# gateway.net
KiCad netlist of a schematic drawn in Altium Designer
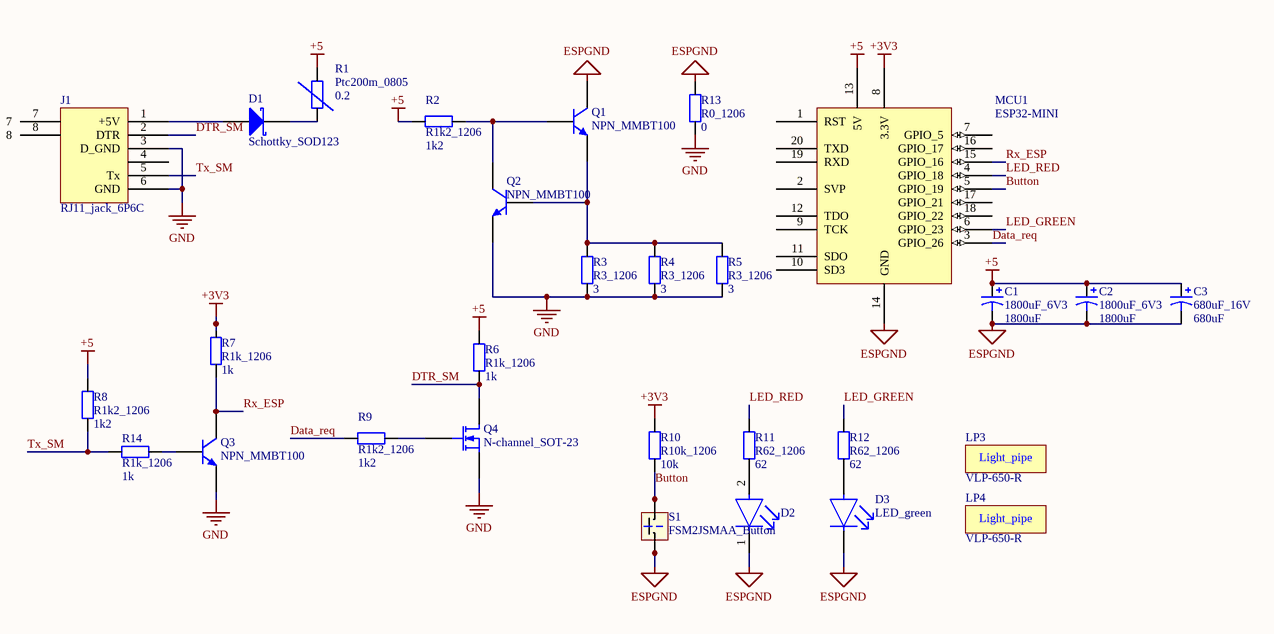
[diagram p0: gateway.SchDoc]

(export (version "E")
  (design (tool "Eeschema 10.0.6"))
  (components
    (comp (ref "C1")
      (value "1800uF_6V3")
      (footprint "CAPAE109103X105M_680uF")
      (description "SMD Aluminium Electrolytic Capacitor, Radial Can, 1800 µF, 10 V, 0.092 ohm, TRV Series")
      (fields
        (field (name "MANUFACTURER PART NUMBER") "EEE-FN0J182UV")
        (field (name "MANUFACTURER") "Panasonic")
        (field (name "ALTIUM_VALUE") "1800uF")
      )
      (libsource (lib "Capacitor") (part "1800uF_6V3"))
    )
    (comp (ref "C2")
      (value "1800uF_6V3")
      (footprint "CAPAE109103X105M_680uF")
      (description "SMD Aluminium Electrolytic Capacitor, Radial Can, 1800 µF, 10 V, 0.092 ohm, TRV Series")
      (fields
        (field (name "MANUFACTURER PART NUMBER") "EEE-FN0J182UV")
        (field (name "MANUFACTURER") "Panasonic")
        (field (name "ALTIUM_VALUE") "1800uF")
      )
      (libsource (lib "Capacitor") (part "1800uF_6V3"))
    )
    (comp (ref "C3")
      (value "680uF_16V")
      (footprint "CAPAE109103X105M_680uF")
      (description "Aluminum Electrolytic Capacitors - SMD LOW ESR ELECTROLYTIC CAPACITORS")
      (fields
        (field (name "MANUFACTURER PART NUMBER") "16TZV680M10X10.5")
        (field (name "MANUFACTURER") "Rubycon")
        (field (name "ALTIUM_VALUE") "680uF")
      )
      (libsource (lib "Capacitor") (part "680uF_16V"))
    )
    (comp (ref "D1")
      (value "Schottky_SOD123")
      (footprint "Diode_SOD-123")
      (description "Schottky Rectifier, 20 V, 500 mA, Single, SOD-123, 2 Pins, 320 mV")
      (fields
        (field (name "MANUFACTURER PART NUMBER") "STPS0520Z")
        (field (name "MANUFACTURER") "STMicroelectronics")
      )
      (libsource (lib "Diodes") (part "Schottky_SOD123"))
    )
    (comp (ref "D2")
      (value "red led")
      (footprint "Kingbright_KPT-2012EC_0")
      (description "KPT-2012EC -  LED, Low Power, Red, SMD, 0805 [2012 Metric], 30 mA, 2 V, 617 nm")
      (fields
        (field (name "MANUFACTURER PART NUMBER") "AP2012SRCPRV")
        (field (name "MANUFACTURER") "Kingbright")
      )
      (libsource (lib "Button_led") (part "KPT-2012EC"))
    )
    (comp (ref "D3")
      (value "LED_green")
      (footprint "Kingbright_KPT-2012EC_0")
      (description "Standard LEDs - SMD GRN WATER CLEAR 0805")
      (fields
        (field (name "MANUFACTURER") "Kingbright")
        (field (name "MANUFACTURER PART NUMBER") "AP2012MGC")
      )
      (libsource (lib "Button_led") (part "LED_green"))
    )
    (comp (ref "J1")
      (value "RJ11_jack_6P6C")
      (footprint "44144-0005")
      (description "Modular Connector, RJ11 Jack, 1 x 1 (Port), 6P6C, Cat3, Surface Mount")
      (fields (field (name "MANUFACTURER PART NUMBER") "44144-0005") (field (name "MANUFACTURER") "Molex"))
      (libsource (lib "Connectors") (part "RJ11_jack_6P6C"))
    )
    (comp (ref "LP3")
      (value "VLP-650-R")
      (footprint "VLP-650-R")
      (description "LED Light Pipes Light Pipe Bd Mount SMD .65\" Round Face")
      (fields (field (name "MANUFACTURER") "Bivar"))
      (libsource (lib "Button_led") (part "VLP-650-R"))
    )
    (comp (ref "LP4")
      (value "VLP-650-R")
      (footprint "VLP-650-R")
      (description "LED Light Pipes Light Pipe Bd Mount SMD .65\" Round Face")
      (fields (field (name "MANUFACTURER") "Bivar"))
      (libsource (lib "Button_led") (part "VLP-650-R"))
    )
    (comp (ref "MCU1")
      (value "ESP32-MINI")
      (footprint "PINHEADERS_SMD_10")
      (description "LilyGO TTGO T7 Mini32 V1.4 ESP32-WROVER")
      (fields (field (name "MANUFACTURER PART NUMBER") "10129380-910002ALF"))
      (libsource (lib "mcu") (part "ESP32-MINI"))
    )
    (comp (ref "Q1")
      (value "NPN_MMBT100")
      (footprint "SOT95P245X110-3N")
      (description "Bipolar (BJT) Single Transistor, NPN, 45 V, 500 mA, 350 mW, SOT-23, Surface Mount")
      (fields
        (field (name "MANUFACTURER PART NUMBER") "MMBT100")
        (field (name "MANUFACTURER") "ON Semiconductor / Fairchild")
      )
      (libsource (lib "Transistor") (part "NPN_MMBT100"))
    )
    (comp (ref "Q2")
      (value "NPN_MMBT100")
      (footprint "SOT95P245X110-3N")
      (description "Bipolar (BJT) Single Transistor, NPN, 45 V, 500 mA, 350 mW, SOT-23, Surface Mount")
      (fields
        (field (name "MANUFACTURER PART NUMBER") "MMBT100")
        (field (name "MANUFACTURER") "ON Semiconductor / Fairchild")
      )
      (libsource (lib "Transistor") (part "NPN_MMBT100"))
    )
    (comp (ref "Q3")
      (value "NPN_MMBT100")
      (footprint "SOT95P245X110-3N")
      (description "Bipolar (BJT) Single Transistor, NPN, 45 V, 500 mA, 350 mW, SOT-23, Surface Mount")
      (fields
        (field (name "MANUFACTURER PART NUMBER") "MMBT100")
        (field (name "MANUFACTURER") "ON Semiconductor / Fairchild")
      )
      (libsource (lib "Transistor") (part "NPN_MMBT100"))
    )
    (comp (ref "Q4")
      (value "N-channel_SOT-23")
      (footprint "SOT95P237X110-3N")
      (description "Power MOSFET, N Channel, 60 V, 260 mA, 1 ohm, SOT-23, Surface Mount")
      (fields
        (field (name "MANUFACTURER PART NUMBER") "NTR5103NT1G")
        (field (name "MANUFACTURER") "ON Semiconductor")
      )
      (libsource (lib "Mosfet") (part "N-channel_SOT-23"))
    )
    (comp (ref "R1")
      (value "Ptc200m_0805")
      (footprint "R0805")
      (description "Thermistor, PTC, SMD, 0805, 0.2 OHM")
      (fields
        (field (name "MANUFACTURER PART NUMBER") "PRG21BC0R2MM1RA")
        (field (name "MANUFACTURER") "Murata")
        (field (name "ALTIUM_VALUE") "0.2")
      )
      (libsource (lib "Resistor") (part "Ptc200m_0805"))
    )
    (comp (ref "R2")
      (value "R1k2_1206")
      (footprint "R1206")
      (description "Thick Film Resistors - SMD 1206 1.2Kohms 1% AEC-Q200")
      (fields
        (field (name "MANUFACTURER") "Panasonic")
        (field (name "MANUFACTURER PART NUMBER") "ERJ-8ENF1201V")
        (field (name "ALTIUM_VALUE") "1k2")
      )
      (libsource (lib "") (part "R1k2_1206_1"))
    )
    (comp (ref "R3")
      (value "R3_1206")
      (footprint "R1206")
      (description "Current Sense Resistors - SMD 1206 3.0ohm 1% Curr Sense AEC-Q200")
      (fields
        (field (name "MANUFACTURER PART NUMBER") "ERJ8RQF3R0V")
        (field (name "MANUFACTURER") "Panasonic")
        (field (name "ALTIUM_VALUE") "3")
      )
      (libsource (lib "Resistor") (part "R3_1206"))
    )
    (comp (ref "R4")
      (value "R3_1206")
      (footprint "R1206")
      (description "Current Sense Resistors - SMD 1206 3.0ohm 1% Curr Sense AEC-Q200")
      (fields
        (field (name "MANUFACTURER PART NUMBER") "ERJ8RQF3R0V")
        (field (name "MANUFACTURER") "Panasonic")
        (field (name "ALTIUM_VALUE") "3")
      )
      (libsource (lib "Resistor") (part "R3_1206"))
    )
    (comp (ref "R5")
      (value "R3_1206")
      (footprint "R1206")
      (description "Current Sense Resistors - SMD 1206 3.0ohm 1% Curr Sense AEC-Q200")
      (fields
        (field (name "MANUFACTURER PART NUMBER") "ERJ8RQF3R0V")
        (field (name "MANUFACTURER") "Panasonic")
        (field (name "ALTIUM_VALUE") "3")
      )
      (libsource (lib "Resistor") (part "R3_1206"))
    )
    (comp (ref "R6")
      (value "R1k_1206")
      (footprint "R1206")
      (description "Thick Film Resistors - SMD 1206 1Kohms 1% Tol AEC-Q200")
      (fields
        (field (name "TOLERANCE") "1%")
        (field (name "MANUFACTURER PART NUMBER") "ERJ-8ENF1001V")
        (field (name "ALTIUM_VALUE") "1k")
      )
      (libsource (lib "Resistor") (part "R1k_1206"))
    )
    (comp (ref "R7")
      (value "R1k_1206")
      (footprint "R1206")
      (description "Thick Film Resistors - SMD 1206 1Kohms 1% Tol AEC-Q200")
      (fields
        (field (name "TOLERANCE") "1%")
        (field (name "MANUFACTURER PART NUMBER") "ERJ-8ENF1001V")
        (field (name "ALTIUM_VALUE") "1k")
      )
      (libsource (lib "Resistor") (part "R1k_1206"))
    )
    (comp (ref "R8")
      (value "R1k2_1206")
      (footprint "R1206")
      (description "Thick Film Resistors - SMD 1206 1.2Kohms 1% AEC-Q200")
      (fields
        (field (name "MANUFACTURER") "Panasonic")
        (field (name "MANUFACTURER PART NUMBER") "ERJ-8ENF1201V")
        (field (name "ALTIUM_VALUE") "1k2")
      )
      (libsource (lib "Resistor") (part "R1k2_1206"))
    )
    (comp (ref "R9")
      (value "R1k2_1206")
      (footprint "R1206")
      (description "Thick Film Resistors - SMD 1206 1.2Kohms 1% AEC-Q200")
      (fields
        (field (name "MANUFACTURER") "Panasonic")
        (field (name "MANUFACTURER PART NUMBER") "ERJ-8ENF1201V")
        (field (name "ALTIUM_VALUE") "1k2")
      )
      (libsource (lib "") (part "R1k2_1206_1"))
    )
    (comp (ref "R10")
      (value "R10k_1206")
      (footprint "R1206")
      (description "Thick Film Resistors - SMD 1206 10Kohms 1% AEC-Q200")
      (fields
        (field (name "TOLERANCE") "1%")
        (field (name "MANUFACTURER PART NUMBER") "ERJ-8ENF1002V")
        (field (name "ALTIUM_VALUE") "10k")
      )
      (libsource (lib "Resistor") (part "R10k_1206"))
    )
    (comp (ref "R11")
      (value "R62_1206")
      (footprint "R1206")
      (description "Thick Film Resistors - SMD 1206 62ohms 1% AEC-Q200")
      (fields
        (field (name "TOLERANCE") "1%")
        (field (name "MANUFACTURER PART NUMBER") "ERJ-8ENF62R0V")
        (field (name "ALTIUM_VALUE") "62")
      )
      (libsource (lib "Resistor") (part "R62_1206"))
    )
    (comp (ref "R12")
      (value "R62_1206")
      (footprint "R1206")
      (description "Thick Film Resistors - SMD 1206 62ohms 1% AEC-Q200")
      (fields
        (field (name "TOLERANCE") "1%")
        (field (name "MANUFACTURER PART NUMBER") "ERJ-8ENF62R0V")
        (field (name "ALTIUM_VALUE") "62")
      )
      (libsource (lib "Resistor") (part "R62_1206"))
    )
    (comp (ref "R13")
      (value "R0_1206")
      (footprint "R1206")
      (fields (field (name "ALTIUM_VALUE") "0"))
      (libsource (lib "Resistor") (part "R0_1206"))
    )
    (comp (ref "R14")
      (value "R1k_1206")
      (footprint "R1206")
      (description "Thick Film Resistors - SMD 1206 1Kohms 1% Tol AEC-Q200")
      (fields
        (field (name "TOLERANCE") "1%")
        (field (name "MANUFACTURER PART NUMBER") "ERJ-8ENF1001V")
        (field (name "ALTIUM_VALUE") "1k")
      )
      (libsource (lib "") (part "R1k_1206_1"))
    )
    (comp (ref "S1")
      (value "FSM2JSMAA_Button")
      (footprint "FP-FSM2JSMAA-MFG")
      (description "Tactile Switch, FSMJSM Series, Top Actuated, Surface Mount, Round Button, 260 gf, 50mA at 24VDC")
      (fields
        (field (name "MANUFACTURER PART NUMBER") "FSM2JSMAA")
        (field (name "MANUFACTURER") "TE Connectivity")
      )
      (libsource (lib "Button_led") (part "FSM2JSMAA_Button"))
    )
  )
  (nets
    (net (code "1") (name "+3V3") (class "Default")
      (node (ref "MCU1") (pin "8") (pinfunction "3.3V_8") (pintype "power_in"))
      (node (ref "R10") (pin "2") (pinfunction "2_2") (pintype "passive"))
      (node (ref "R7") (pin "2") (pinfunction "2_2") (pintype "passive"))
    )
    (net (code "2") (name "+5") (class "Default")
      (node (ref "C1") (pin "1") (pinfunction "1_1") (pintype "passive"))
      (node (ref "C2") (pin "1") (pinfunction "1_1") (pintype "passive"))
      (node (ref "C3") (pin "1") (pinfunction "1_1") (pintype "passive"))
      (node (ref "MCU1") (pin "13") (pinfunction "5V_13") (pintype "power_in"))
      (node (ref "R1") (pin "2") (pinfunction "2_2") (pintype "passive"))
      (node (ref "R2") (pin "1") (pinfunction "1_1") (pintype "passive"))
      (node (ref "R6") (pin "2") (pinfunction "2_2") (pintype "passive"))
      (node (ref "R8") (pin "2") (pinfunction "2_2") (pintype "passive"))
    )
    (net (code "3") (name "/Button") (class "Default")
      (node (ref "MCU1") (pin "5") (pinfunction "GPIO_19_5") (pintype "bidirectional"))
      (node (ref "R10") (pin "1") (pinfunction "1_1") (pintype "passive"))
      (node (ref "S1") (pin "2") (pinfunction "b_2") (pintype "passive"))
      (node (ref "S1") (pin "4") (pinfunction "d_4") (pintype "passive"))
    )
    (net (code "4") (name "/DTR_SM") (class "Default")
      (node (ref "J1") (pin "2") (pinfunction "DTR_2") (pintype "passive"))
      (node (ref "Q4") (pin "1") (pinfunction "D_1") (pintype "passive"))
      (node (ref "R6") (pin "1") (pinfunction "1_1") (pintype "passive"))
    )
    (net (code "5") (name "/Data_req") (class "Default")
      (node (ref "MCU1") (pin "3") (pinfunction "GPIO_26_3") (pintype "bidirectional"))
      (node (ref "R9") (pin "1") (pinfunction "1_1") (pintype "passive"))
    )
    (net (code "6") (name "/LED_GREEN") (class "Default")
      (node (ref "MCU1") (pin "6") (pinfunction "GPIO_23_6") (pintype "bidirectional"))
      (node (ref "R12") (pin "2") (pinfunction "2_2") (pintype "passive"))
    )
    (net (code "7") (name "/LED_RED") (class "Default")
      (node (ref "MCU1") (pin "4") (pinfunction "GPIO_18_4") (pintype "bidirectional"))
      (node (ref "R11") (pin "2") (pinfunction "2_2") (pintype "passive"))
    )
    (net (code "8") (name "/Rx_ESP") (class "Default")
      (node (ref "MCU1") (pin "15") (pinfunction "GPIO_16_15") (pintype "bidirectional"))
      (node (ref "Q3") (pin "3") (pinfunction "C_3") (pintype "passive"))
      (node (ref "R7") (pin "1") (pinfunction "1_1") (pintype "passive"))
    )
    (net (code "9") (name "/Tx_SM") (class "Default")
      (node (ref "J1") (pin "5") (pinfunction "Tx_5") (pintype "passive"))
      (node (ref "R14") (pin "1") (pinfunction "1_1") (pintype "passive"))
      (node (ref "R8") (pin "1") (pinfunction "1_1") (pintype "passive"))
    )
    (net (code "10") (name "ESPGND") (class "Default")
      (node (ref "C1") (pin "2") (pinfunction "2_2") (pintype "passive"))
      (node (ref "C2") (pin "2") (pinfunction "2_2") (pintype "passive"))
      (node (ref "C3") (pin "2") (pinfunction "2_2") (pintype "passive"))
      (node (ref "D2") (pin "1") (pinfunction "C_1") (pintype "passive"))
      (node (ref "D3") (pin "1") (pinfunction "C_1") (pintype "passive"))
      (node (ref "MCU1") (pin "14") (pinfunction "GND_14") (pintype "power_in"))
      (node (ref "Q1") (pin "3") (pinfunction "C_3") (pintype "passive"))
      (node (ref "R13") (pin "2") (pinfunction "2_2") (pintype "passive"))
      (node (ref "S1") (pin "1") (pinfunction "a_1") (pintype "passive"))
      (node (ref "S1") (pin "3") (pinfunction "c_3") (pintype "passive"))
    )
    (net (code "11") (name "GND") (class "Default")
      (node (ref "J1") (pin "3") (pinfunction "D_GND_3") (pintype "power_in"))
      (node (ref "J1") (pin "6") (pinfunction "GND_6") (pintype "power_in"))
      (node (ref "Q2") (pin "1") (pinfunction "E_1") (pintype "passive"))
      (node (ref "Q3") (pin "1") (pinfunction "E_1") (pintype "passive"))
      (node (ref "Q4") (pin "3") (pinfunction "S_3") (pintype "passive"))
      (node (ref "R13") (pin "1") (pinfunction "1_1") (pintype "passive"))
      (node (ref "R3") (pin "1") (pinfunction "1_1") (pintype "passive"))
      (node (ref "R4") (pin "1") (pinfunction "1_1") (pintype "passive"))
      (node (ref "R5") (pin "1") (pinfunction "1_1") (pintype "passive"))
    )
    (net (code "12") (name "Net-(D1-A)") (class "Default")
      (node (ref "D1") (pin "2") (pinfunction "A_2") (pintype "passive"))
      (node (ref "J1") (pin "1") (pinfunction "+5V_1") (pintype "power_in"))
    )
    (net (code "13") (name "Net-(D1-K)") (class "Default")
      (node (ref "D1") (pin "1") (pinfunction "K_1") (pintype "passive"))
      (node (ref "R1") (pin "1") (pinfunction "1_1") (pintype "passive"))
    )
    (net (code "14") (name "Net-(D2-A)") (class "Default")
      (node (ref "D2") (pin "2") (pinfunction "A_2") (pintype "passive"))
      (node (ref "R11") (pin "1") (pinfunction "1_1") (pintype "passive"))
    )
    (net (code "15") (name "Net-(D3-A)") (class "Default")
      (node (ref "D3") (pin "2") (pinfunction "A_2") (pintype "passive"))
      (node (ref "R12") (pin "1") (pinfunction "1_1") (pintype "passive"))
    )
    (net (code "16") (name "Net-(Q1-B)") (class "Default")
      (node (ref "Q1") (pin "2") (pinfunction "B_2") (pintype "passive"))
      (node (ref "Q2") (pin "3") (pinfunction "C_3") (pintype "passive"))
      (node (ref "R2") (pin "2") (pinfunction "2_2") (pintype "passive"))
    )
    (net (code "17") (name "Net-(Q1-E)") (class "Default")
      (node (ref "Q1") (pin "1") (pinfunction "E_1") (pintype "passive"))
      (node (ref "Q2") (pin "2") (pinfunction "B_2") (pintype "passive"))
      (node (ref "R3") (pin "2") (pinfunction "2_2") (pintype "passive"))
      (node (ref "R4") (pin "2") (pinfunction "2_2") (pintype "passive"))
      (node (ref "R5") (pin "2") (pinfunction "2_2") (pintype "passive"))
    )
    (net (code "18") (name "Net-(Q3-B)") (class "Default")
      (node (ref "Q3") (pin "2") (pinfunction "B_2") (pintype "passive"))
      (node (ref "R14") (pin "2") (pinfunction "2_2") (pintype "passive"))
    )
    (net (code "19") (name "Net-(Q4-G)") (class "Default")
      (node (ref "Q4") (pin "2") (pinfunction "G_2") (pintype "passive"))
      (node (ref "R9") (pin "2") (pinfunction "2_2") (pintype "passive"))
    )
    (net (code "20") (name "unconnected-(J1-Pad4)") (class "Default")
      (node (ref "J1") (pin "4") (pintype "passive"))
    )
    (net (code "21") (name "unconnected-(J1-Pad7)") (class "Default")
      (node (ref "J1") (pin "7") (pinfunction "7_7") (pintype "passive"))
    )
    (net (code "22") (name "unconnected-(J1-Pad8)") (class "Default")
      (node (ref "J1") (pin "8") (pinfunction "8_8") (pintype "passive"))
    )
    (net (code "23") (name "unconnected-(MCU1-GPIO_5-Pad7)") (class "Default")
      (node (ref "MCU1") (pin "7") (pinfunction "GPIO_5_7") (pintype "bidirectional"))
    )
    (net (code "24") (name "unconnected-(MCU1-GPIO_17-Pad16)") (class "Default")
      (node (ref "MCU1") (pin "16") (pinfunction "GPIO_17_16") (pintype "bidirectional"))
    )
    (net (code "25") (name "unconnected-(MCU1-GPIO_21-Pad17)") (class "Default")
      (node (ref "MCU1") (pin "17") (pinfunction "GPIO_21_17") (pintype "bidirectional"))
    )
    (net (code "26") (name "unconnected-(MCU1-GPIO_22-Pad18)") (class "Default")
      (node (ref "MCU1") (pin "18") (pinfunction "GPIO_22_18") (pintype "bidirectional"))
    )
    (net (code "27") (name "unconnected-(MCU1-RST-Pad1)") (class "Default")
      (node (ref "MCU1") (pin "1") (pinfunction "RST_1") (pintype "passive"))
    )
    (net (code "28") (name "unconnected-(MCU1-RXD-Pad19)") (class "Default")
      (node (ref "MCU1") (pin "19") (pinfunction "RXD_19") (pintype "passive"))
    )
    (net (code "29") (name "unconnected-(MCU1-SD3-Pad10)") (class "Default")
      (node (ref "MCU1") (pin "10") (pinfunction "SD3_10") (pintype "passive"))
    )
    (net (code "30") (name "unconnected-(MCU1-SDO-Pad11)") (class "Default")
      (node (ref "MCU1") (pin "11") (pinfunction "SDO_11") (pintype "passive"))
    )
    (net (code "31") (name "unconnected-(MCU1-SVP-Pad2)") (class "Default")
      (node (ref "MCU1") (pin "2") (pinfunction "SVP_2") (pintype "passive"))
    )
    (net (code "32") (name "unconnected-(MCU1-TCK-Pad9)") (class "Default")
      (node (ref "MCU1") (pin "9") (pinfunction "TCK_9") (pintype "passive"))
    )
    (net (code "33") (name "unconnected-(MCU1-TDO-Pad12)") (class "Default")
      (node (ref "MCU1") (pin "12") (pinfunction "TDO_12") (pintype "passive"))
    )
    (net (code "34") (name "unconnected-(MCU1-TXD-Pad20)") (class "Default")
      (node (ref "MCU1") (pin "20") (pinfunction "TXD_20") (pintype "passive"))
    )
  )
)
